# MINI_SAM_D51_005.net
KiCad netlist of a schematic drawn in EAGLE
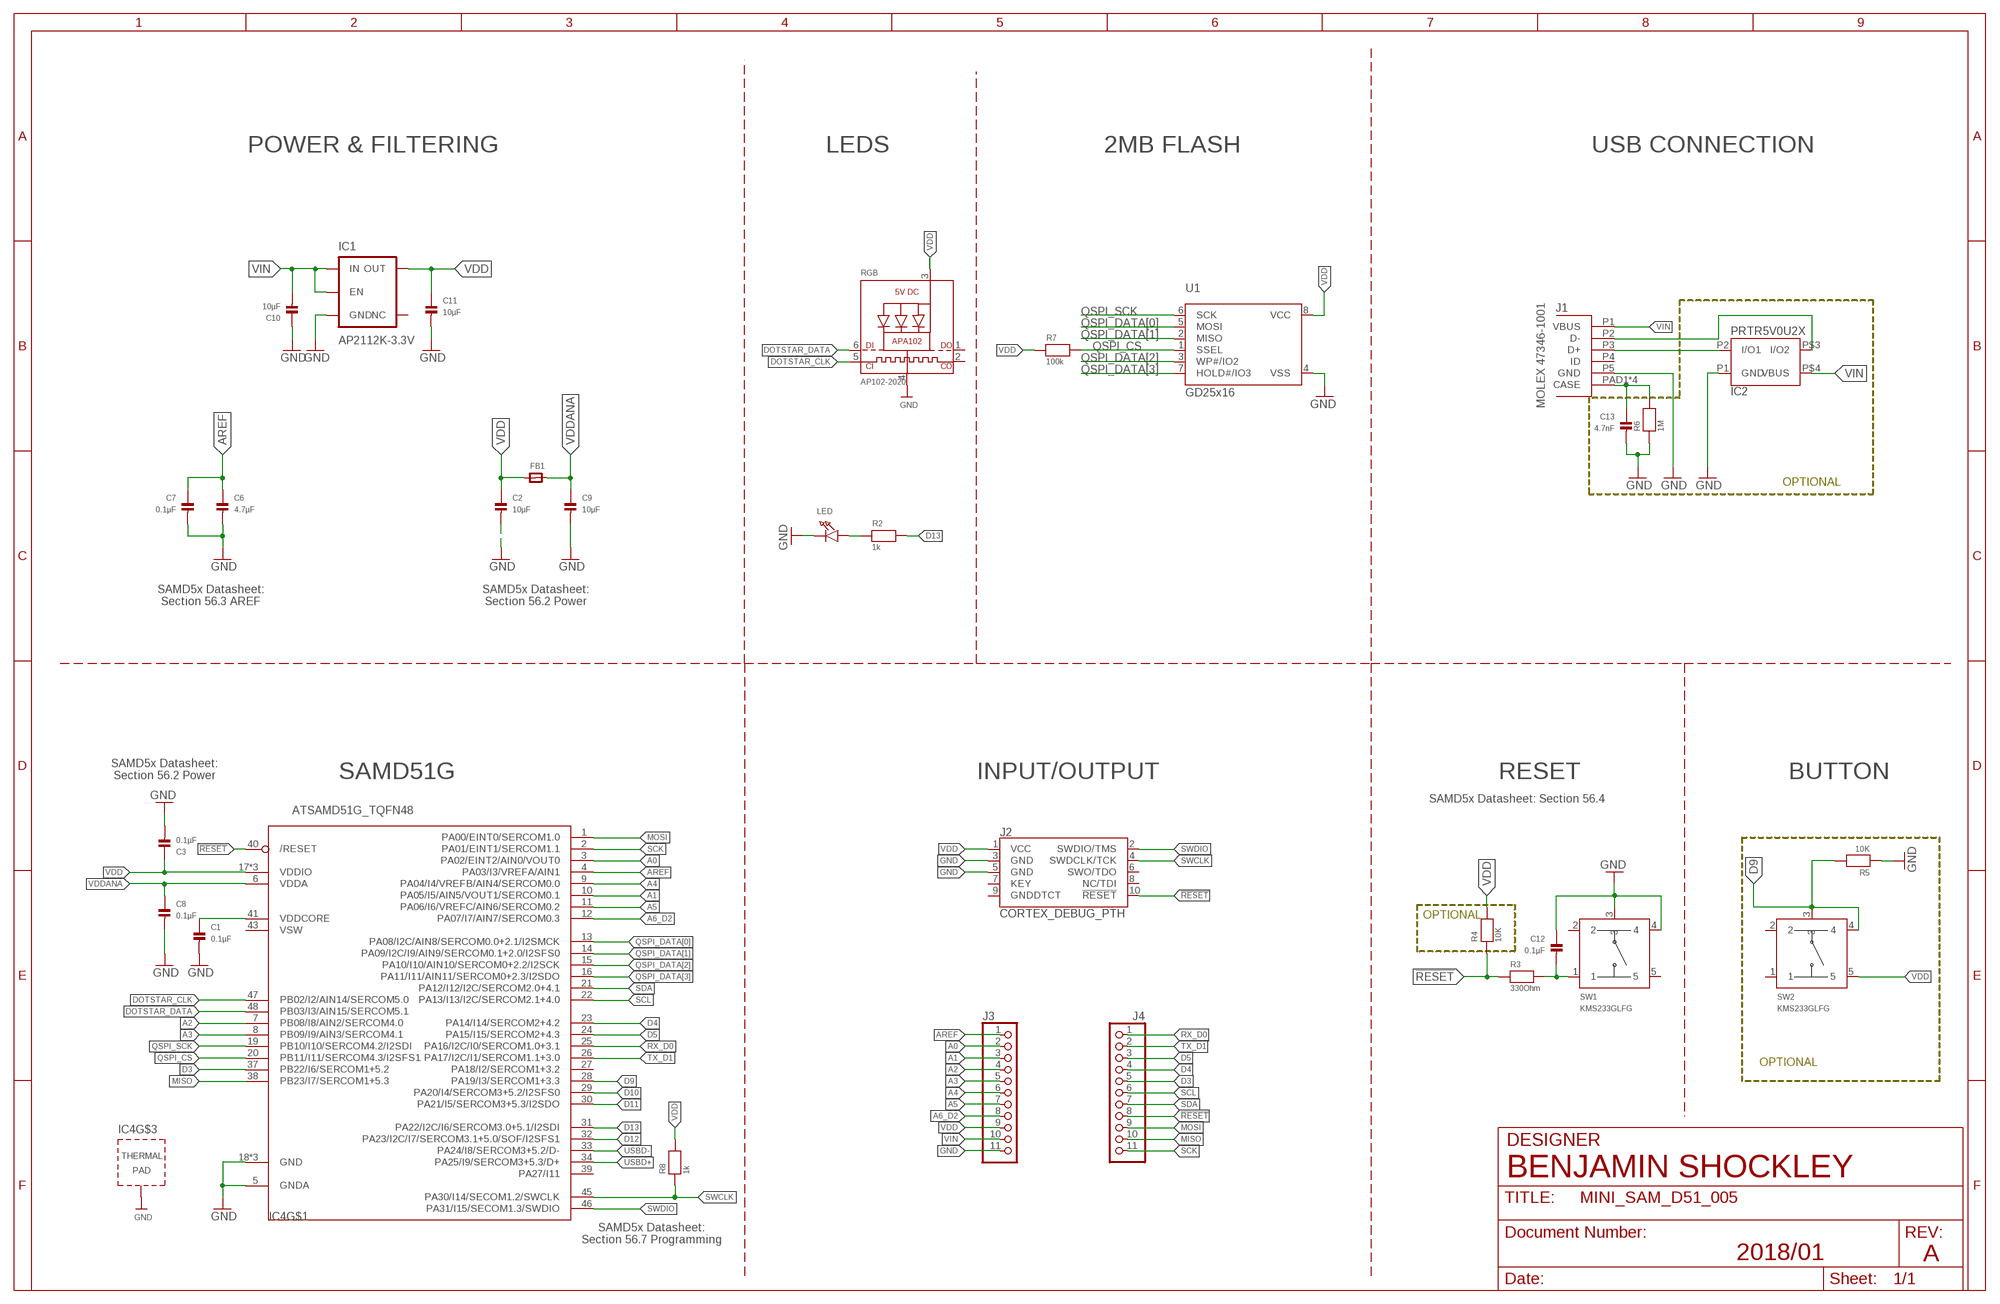
[diagram p0: schematic, sheet 1]

(export (version "E")
  (design (tool "Eeschema 10.0.6"))
  (components
    (comp (ref "C1")
      (value "0.1µF")
      (footprint "eagle-import:_0603MP")
      (libsource (lib "eagle-import") (part "CAP_CERAMIC_0603MP"))
    )
    (comp (ref "C2")
      (value "10µF")
      (footprint "eagle-import:_0603MP")
      (libsource (lib "eagle-import") (part "CAP_CERAMIC_0603MP"))
    )
    (comp (ref "C3")
      (value "0.1µF")
      (footprint "eagle-import:_0603MP")
      (libsource (lib "eagle-import") (part "CAP_CERAMIC_0603MP"))
    )
    (comp (ref "C6")
      (value "4.7µF")
      (footprint "eagle-import:_0603MP")
      (libsource (lib "eagle-import") (part "CAP_CERAMIC_0603MP"))
    )
    (comp (ref "C7")
      (value "0.1µF")
      (footprint "eagle-import:_0603MP")
      (libsource (lib "eagle-import") (part "CAP_CERAMIC_0603MP"))
    )
    (comp (ref "C8")
      (value "0.1µF")
      (footprint "eagle-import:_0603MP")
      (libsource (lib "eagle-import") (part "CAP_CERAMIC_0603MP"))
    )
    (comp (ref "C9")
      (value "10µF")
      (footprint "eagle-import:_0603MP")
      (libsource (lib "eagle-import") (part "CAP_CERAMIC_0603MP"))
    )
    (comp (ref "C10")
      (value "10µF")
      (footprint "eagle-import:_0603MP")
      (libsource (lib "eagle-import") (part "CAP_CERAMIC_0603MP"))
    )
    (comp (ref "C11")
      (value "10µF")
      (footprint "eagle-import:_0603MP")
      (libsource (lib "eagle-import") (part "CAP_CERAMIC_0603MP"))
    )
    (comp (ref "C12")
      (value "0.1µF")
      (footprint "eagle-import:_0603MP")
      (libsource (lib "eagle-import") (part "CAP_CERAMIC_0603MP"))
    )
    (comp (ref "C13")
      (value "4.7nF")
      (footprint "eagle-import:_0603MP")
      (libsource (lib "eagle-import") (part "CAP_CERAMIC_0603MP"))
    )
    (comp (ref "FB1")
      (value "FERRITE_0603MP")
      (footprint "eagle-import:_0603MP")
      (libsource (lib "eagle-import") (part "FERRITE_0603MP"))
    )
    (comp (ref "IC1")
      (value "AP2112K-3.3V")
      (footprint "eagle-import:SOT23-5")
      (libsource (lib "eagle-import") (part "V_REG_AP2112K-3.3V"))
    )
    (comp (ref "IC2")
      (value "PRTR5V0U2X")
      (footprint "eagle-import:SOT143B_REFLOW")
      (libsource (lib "eagle-import") (part "PRTR5V0U2X"))
    )
    (comp (ref "IC4")
      (value "ATSAMD51G_TQFN48")
      (footprint "eagle-import:TQFN48_7MM")
      (libsource (lib "eagle-import") (part "ATSAMD51G_TQFN48"))
    )
    (comp (ref "J1")
      (value "MOLEX_47346-100147346")
      (footprint "eagle-import:MOLEX_47346-1001")
      (libsource (lib "eagle-import") (part "MOLEX_47346-100147346"))
    )
    (comp (ref "J2")
      (value "CORTEX_DEBUG_PTH")
      (footprint "eagle-import:2X5-PTH-1.27MM")
      (libsource (lib "eagle-import") (part "CORTEX_DEBUG_PTH"))
    )
    (comp (ref "J3")
      (value "PINHD-1X111X11_SMT")
      (footprint "eagle-import:1X11_SMT")
      (libsource (lib "eagle-import") (part "PINHD-1X111X11_SMT"))
    )
    (comp (ref "J4")
      (value "PINHD-1X111X11_SMT")
      (footprint "eagle-import:1X11_SMT")
      (libsource (lib "eagle-import") (part "PINHD-1X111X11_SMT"))
    )
    (comp (ref "LED")
      (value "LED0603_NOOUTLINE")
      (footprint "eagle-import:CHIPLED_0603_NOOUTLINE")
      (libsource (lib "eagle-import") (part "LED0603_NOOUTLINE"))
    )
    (comp (ref "R2")
      (value "1k")
      (footprint "eagle-import:_0603MP")
      (libsource (lib "eagle-import") (part "RESISTOR_0603MP"))
    )
    (comp (ref "R3")
      (value "330Ohm")
      (footprint "eagle-import:_0603MP")
      (libsource (lib "eagle-import") (part "RESISTOR_0603MP"))
    )
    (comp (ref "R4")
      (value "10K")
      (footprint "eagle-import:_0603MP")
      (libsource (lib "eagle-import") (part "RESISTOR_0603MP"))
    )
    (comp (ref "R5")
      (value "10K")
      (footprint "eagle-import:_0603MP")
      (libsource (lib "eagle-import") (part "RESISTOR_0603MP"))
    )
    (comp (ref "R6")
      (value "1M")
      (footprint "eagle-import:_0603MP")
      (libsource (lib "eagle-import") (part "RESISTOR_0603MP"))
    )
    (comp (ref "R7")
      (value "100k")
      (footprint "eagle-import:_0603MP")
      (libsource (lib "eagle-import") (part "RESISTOR_0603MP"))
    )
    (comp (ref "R8")
      (value "1k")
      (footprint "eagle-import:_0603MP")
      (libsource (lib "eagle-import") (part "RESISTOR_0603MP"))
    )
    (comp (ref "RGB")
      (value "AP102-2020")
      (footprint "eagle-import:APA102_2020")
      (libsource (lib "eagle-import") (part "APA1022020"))
    )
    (comp (ref "SW1")
      (value "KMS233GLFG")
      (footprint "eagle-import:KMS_SWITCH")
      (libsource (lib "eagle-import") (part "KMS_SWITCHKMS"))
    )
    (comp (ref "SW2")
      (value "KMS233GLFG")
      (footprint "eagle-import:KMS_SWITCH")
      (libsource (lib "eagle-import") (part "KMS_SWITCHKMS"))
    )
    (comp (ref "U1")
      (value "GD25x16")
      (footprint "eagle-import:USON8")
      (libsource (lib "eagle-import") (part "SPIFLASH_8PINUX"))
    )
  )
  (nets
    (net (code "1") (name "/VSW") (class "Default")
      (node (ref "IC4") (pin "43") (pinfunction "VSW_43") (pintype "power_in"))
    )
    (net (code "2") (name "/~{RESET}") (class "Default")
      (node (ref "IC4") (pin "40") (pinfunction "/RESET_40") (pintype "bidirectional"))
      (node (ref "J2") (pin "10") (pinfunction "~{RESET}_10") (pintype "bidirectional"))
      (node (ref "J4") (pin "8") (pinfunction "8_8") (pintype "passive"))
      (node (ref "R3") (pin "1") (pinfunction "1_1") (pintype "passive"))
      (node (ref "R4") (pin "1") (pinfunction "1_1") (pintype "passive"))
    )
    (net (code "3") (name "A0") (class "Default")
      (node (ref "IC4") (pin "3") (pinfunction "PA02/EINT2/AIN0/VOUT0_3") (pintype "bidirectional"))
      (node (ref "J3") (pin "2") (pinfunction "2_2") (pintype "passive"))
    )
    (net (code "4") (name "A1") (class "Default")
      (node (ref "IC4") (pin "10") (pinfunction "PA05/I5/AIN5/VOUT1/SERCOM0.1_10") (pintype "bidirectional"))
      (node (ref "J3") (pin "3") (pinfunction "3_3") (pintype "passive"))
    )
    (net (code "5") (name "A2") (class "Default")
      (node (ref "IC4") (pin "7") (pinfunction "PB08/I8/AIN2/SERCOM4.0_7") (pintype "bidirectional"))
      (node (ref "J3") (pin "4") (pinfunction "4_4") (pintype "passive"))
    )
    (net (code "6") (name "A3") (class "Default")
      (node (ref "IC4") (pin "8") (pinfunction "PB09/I9/AIN3/SERCOM4.1_8") (pintype "bidirectional"))
      (node (ref "J3") (pin "5") (pinfunction "5_5") (pintype "passive"))
    )
    (net (code "7") (name "A4") (class "Default")
      (node (ref "IC4") (pin "9") (pinfunction "PA04/I4/VREFB/AIN4/SERCOM0.0_9") (pintype "bidirectional"))
      (node (ref "J3") (pin "6") (pinfunction "6_6") (pintype "passive"))
    )
    (net (code "8") (name "A5") (class "Default")
      (node (ref "IC4") (pin "11") (pinfunction "PA06/I6/VREFC/AIN6/SERCOM0.2_11") (pintype "bidirectional"))
      (node (ref "J3") (pin "7") (pinfunction "7_7") (pintype "passive"))
    )
    (net (code "9") (name "A6_D2") (class "Default")
      (node (ref "IC4") (pin "12") (pinfunction "PA07/I7/AIN7/SERCOM0.3_12") (pintype "bidirectional"))
      (node (ref "J3") (pin "8") (pinfunction "8_8") (pintype "passive"))
    )
    (net (code "10") (name "AREF") (class "Default")
      (node (ref "C6") (pin "1") (pinfunction "P$1_1") (pintype "passive"))
      (node (ref "C7") (pin "1") (pinfunction "P$1_1") (pintype "passive"))
      (node (ref "IC4") (pin "4") (pinfunction "PA03/I3/VREFA/AIN1_4") (pintype "bidirectional"))
      (node (ref "J3") (pin "1") (pinfunction "1_1") (pintype "passive"))
    )
    (net (code "11") (name "D3") (class "Default")
      (node (ref "IC4") (pin "37") (pinfunction "PB22/I6/SERCOM1+5.2_37") (pintype "bidirectional"))
      (node (ref "J4") (pin "5") (pinfunction "5_5") (pintype "passive"))
    )
    (net (code "12") (name "D4") (class "Default")
      (node (ref "IC4") (pin "23") (pinfunction "PA14/I14/SERCOM2+4.2_23") (pintype "bidirectional"))
      (node (ref "J4") (pin "4") (pinfunction "4_4") (pintype "passive"))
    )
    (net (code "13") (name "D5") (class "Default")
      (node (ref "IC4") (pin "24") (pinfunction "PA15/I15/SERCOM2+4.3_24") (pintype "bidirectional"))
      (node (ref "J4") (pin "3") (pinfunction "3_3") (pintype "passive"))
    )
    (net (code "14") (name "D9") (class "Default")
      (node (ref "IC4") (pin "28") (pinfunction "PA19/I3/SERCOM1+3.3_28") (pintype "bidirectional"))
      (node (ref "R5") (pin "2") (pinfunction "2_2") (pintype "passive"))
      (node (ref "SW2") (pin "3") (pinfunction "3_3") (pintype "bidirectional"))
      (node (ref "SW2") (pin "4") (pinfunction "4_4") (pintype "bidirectional"))
    )
    (net (code "15") (name "D10") (class "Default")
      (node (ref "IC4") (pin "29") (pinfunction "PA20/I4/SERCOM3+5.2/I2SFS0_29") (pintype "bidirectional"))
    )
    (net (code "16") (name "D11") (class "Default")
      (node (ref "IC4") (pin "30") (pinfunction "PA21/I5/SERCOM3+5.3/I2SDO_30") (pintype "bidirectional"))
    )
    (net (code "17") (name "D12") (class "Default")
      (node (ref "IC4") (pin "32") (pinfunction "PA23/I2C/I7/SERCOM3.1+5.0/SOF/I2SFS1_32") (pintype "bidirectional"))
    )
    (net (code "18") (name "D13") (class "Default")
      (node (ref "IC4") (pin "31") (pinfunction "PA22/I2C/I6/SERCOM3.0+5.1/I2SDI_31") (pintype "bidirectional"))
      (node (ref "R2") (pin "2") (pinfunction "2_2") (pintype "passive"))
    )
    (net (code "19") (name "DOTSTAR_CLK") (class "Default")
      (node (ref "IC4") (pin "47") (pinfunction "PB02/I2/AIN14/SERCOM5.0_47") (pintype "bidirectional"))
      (node (ref "RGB") (pin "5") (pinfunction "CKI_5") (pintype "input"))
    )
    (net (code "20") (name "DOTSTAR_DATA") (class "Default")
      (node (ref "IC4") (pin "48") (pinfunction "PB03/I3/AIN15/SERCOM5.1_48") (pintype "bidirectional"))
      (node (ref "RGB") (pin "6") (pinfunction "DI_6") (pintype "input"))
    )
    (net (code "21") (name "GND") (class "Default")
      (node (ref "C1") (pin "2") (pinfunction "P$2_2") (pintype "passive"))
      (node (ref "C10") (pin "1") (pinfunction "P$1_1") (pintype "passive"))
      (node (ref "C11") (pin "2") (pinfunction "P$2_2") (pintype "passive"))
      (node (ref "C12") (pin "1") (pinfunction "P$1_1") (pintype "passive"))
      (node (ref "C13") (pin "2") (pinfunction "P$2_2") (pintype "passive"))
      (node (ref "C2") (pin "2") (pinfunction "P$2_2") (pintype "passive"))
      (node (ref "C3") (pin "2") (pinfunction "P$2_2") (pintype "passive"))
      (node (ref "C6") (pin "2") (pinfunction "P$2_2") (pintype "passive"))
      (node (ref "C7") (pin "2") (pinfunction "P$2_2") (pintype "passive"))
      (node (ref "C8") (pin "2") (pinfunction "P$2_2") (pintype "passive"))
      (node (ref "C9") (pin "2") (pinfunction "P$2_2") (pintype "passive"))
      (node (ref "IC1") (pin "2") (pinfunction "GND_2") (pintype "input"))
      (node (ref "IC2") (pin "P1") (pinfunction "GND_P1") (pintype "bidirectional"))
      (node (ref "IC4") (pin "18") (pinfunction "GND_18") (pintype "power_in"))
      (node (ref "IC4") (pin "35") (pinfunction "GND_35") (pintype "power_in"))
      (node (ref "IC4") (pin "42") (pinfunction "GND_42") (pintype "power_in"))
      (node (ref "IC4") (pin "5") (pinfunction "GNDA_5") (pintype "power_in"))
      (node (ref "IC4") (pin "THERMAL") (pinfunction "TP_THERMAL") (pintype "power_in"))
      (node (ref "J1") (pin "P5") (pinfunction "GND_P5") (pintype "power_in"))
      (node (ref "J2") (pin "3") (pinfunction "GND_3") (pintype "bidirectional"))
      (node (ref "J2") (pin "5") (pinfunction "GND_5") (pintype "bidirectional"))
      (node (ref "J3") (pin "11") (pinfunction "11_11") (pintype "passive"))
      (node (ref "LED") (pin "C") (pinfunction "C_C") (pintype "passive"))
      (node (ref "R5") (pin "1") (pinfunction "1_1") (pintype "passive"))
      (node (ref "R6") (pin "1") (pinfunction "1_1") (pintype "passive"))
      (node (ref "RGB") (pin "4") (pinfunction "GND_4") (pintype "power_in"))
      (node (ref "SW1") (pin "3") (pinfunction "3_3") (pintype "bidirectional"))
      (node (ref "SW1") (pin "4") (pinfunction "4_4") (pintype "bidirectional"))
      (node (ref "U1") (pin "4") (pinfunction "VSS_4") (pintype "bidirectional"))
    )
    (net (code "22") (name "MISO") (class "Default")
      (node (ref "IC4") (pin "38") (pinfunction "PB23/I7/SERCOM1+5.3_38") (pintype "bidirectional"))
      (node (ref "J4") (pin "10") (pinfunction "10_10") (pintype "passive"))
    )
    (net (code "23") (name "MOSI") (class "Default")
      (node (ref "IC4") (pin "1") (pinfunction "PA00/EINT0/SERCOM1.0_1") (pintype "bidirectional"))
      (node (ref "J4") (pin "9") (pinfunction "9_9") (pintype "passive"))
    )
    (net (code "24") (name "Net-(C1-P$1)") (class "Default")
      (node (ref "C1") (pin "1") (pinfunction "P$1_1") (pintype "passive"))
      (node (ref "IC4") (pin "41") (pinfunction "VDDCORE_41") (pintype "power_in"))
    )
    (net (code "25") (name "Net-(C12-P$2)") (class "Default")
      (node (ref "C12") (pin "2") (pinfunction "P$2_2") (pintype "passive"))
      (node (ref "R3") (pin "2") (pinfunction "2_2") (pintype "passive"))
      (node (ref "SW1") (pin "1") (pinfunction "1_1") (pintype "bidirectional"))
    )
    (net (code "26") (name "Net-(C13-P$1)") (class "Default")
      (node (ref "C13") (pin "1") (pinfunction "P$1_1") (pintype "passive"))
      (node (ref "J1") (pin "PAD1") (pinfunction "CASE_PAD1") (pintype "bidirectional"))
      (node (ref "J1") (pin "PAD2") (pinfunction "CASE_PAD2") (pintype "bidirectional"))
      (node (ref "J1") (pin "PAD3") (pinfunction "CASE_PAD3") (pintype "bidirectional"))
      (node (ref "J1") (pin "PAD4") (pinfunction "CASE_PAD4") (pintype "bidirectional"))
      (node (ref "R6") (pin "2") (pinfunction "2_2") (pintype "passive"))
    )
    (net (code "27") (name "Net-(LED-PadA)") (class "Default")
      (node (ref "LED") (pin "A") (pinfunction "A_A") (pintype "passive"))
      (node (ref "R2") (pin "1") (pinfunction "1_1") (pintype "passive"))
    )
    (net (code "28") (name "QSPI_CS") (class "Default")
      (node (ref "IC4") (pin "20") (pinfunction "PB11/I11/SERCOM4.3/I2SFS1_20") (pintype "bidirectional"))
      (node (ref "R7") (pin "2") (pinfunction "2_2") (pintype "passive"))
      (node (ref "U1") (pin "1") (pinfunction "SSEL_1") (pintype "bidirectional"))
    )
    (net (code "29") (name "QSPI_DATA[0]") (class "Default")
      (node (ref "IC4") (pin "13") (pinfunction "PA08/I2C/AIN8/SERCOM0.0+2.1/I2SMCK_13") (pintype "bidirectional"))
      (node (ref "U1") (pin "5") (pinfunction "MOSI_5") (pintype "bidirectional"))
    )
    (net (code "30") (name "QSPI_DATA[1]") (class "Default")
      (node (ref "IC4") (pin "14") (pinfunction "PA09/I2C/I9/AIN9/SERCOM0.1+2.0/I2SFS0_14") (pintype "bidirectional"))
      (node (ref "U1") (pin "2") (pinfunction "MISO_2") (pintype "bidirectional"))
    )
    (net (code "31") (name "QSPI_DATA[2]") (class "Default")
      (node (ref "IC4") (pin "15") (pinfunction "PA10/I10/AIN10/SERCOM0+2.2/I2SCK_15") (pintype "bidirectional"))
      (node (ref "U1") (pin "3") (pinfunction "WP#/IO2_3") (pintype "bidirectional"))
    )
    (net (code "32") (name "QSPI_DATA[3]") (class "Default")
      (node (ref "IC4") (pin "16") (pinfunction "PA11/I11/AIN11/SERCOM0+2.3/I2SDO_16") (pintype "bidirectional"))
      (node (ref "U1") (pin "7") (pinfunction "HOLD#/IO3_7") (pintype "bidirectional"))
    )
    (net (code "33") (name "QSPI_SCK") (class "Default")
      (node (ref "IC4") (pin "19") (pinfunction "PB10/I10/SERCOM4.2/I2SDI_19") (pintype "bidirectional"))
      (node (ref "U1") (pin "6") (pinfunction "SCK_6") (pintype "bidirectional"))
    )
    (net (code "34") (name "RX_D0") (class "Default")
      (node (ref "IC4") (pin "25") (pinfunction "PA16/I2C/I0/SERCOM1.0+3.1_25") (pintype "bidirectional"))
      (node (ref "J4") (pin "1") (pinfunction "1_1") (pintype "passive"))
    )
    (net (code "35") (name "SCK") (class "Default")
      (node (ref "IC4") (pin "2") (pinfunction "PA01/EINT1/SERCOM1.1_2") (pintype "bidirectional"))
      (node (ref "J4") (pin "11") (pinfunction "11_11") (pintype "passive"))
    )
    (net (code "36") (name "SCL") (class "Default")
      (node (ref "IC4") (pin "22") (pinfunction "PA13/I13/I2C/SERCOM2.1+4.0_22") (pintype "bidirectional"))
      (node (ref "J4") (pin "6") (pinfunction "6_6") (pintype "passive"))
    )
    (net (code "37") (name "SDA") (class "Default")
      (node (ref "IC4") (pin "21") (pinfunction "PA12/I12/I2C/SERCOM2.0+4.1_21") (pintype "bidirectional"))
      (node (ref "J4") (pin "7") (pinfunction "7_7") (pintype "passive"))
    )
    (net (code "38") (name "SWCLK") (class "Default")
      (node (ref "IC4") (pin "45") (pinfunction "PA30/I14/SECOM1.2/SWCLK_45") (pintype "bidirectional"))
      (node (ref "J2") (pin "4") (pinfunction "SWDCLK/TCK_4") (pintype "bidirectional"))
      (node (ref "R8") (pin "1") (pinfunction "1_1") (pintype "passive"))
    )
    (net (code "39") (name "SWDIO") (class "Default")
      (node (ref "IC4") (pin "46") (pinfunction "PA31/I15/SECOM1.3/SWDIO_46") (pintype "bidirectional"))
      (node (ref "J2") (pin "2") (pinfunction "SWDIO/TMS_2") (pintype "bidirectional"))
    )
    (net (code "40") (name "TX_D1") (class "Default")
      (node (ref "IC4") (pin "26") (pinfunction "PA17/I2C/I1/SERCOM1.1+3.0_26") (pintype "bidirectional"))
      (node (ref "J4") (pin "2") (pinfunction "2_2") (pintype "passive"))
    )
    (net (code "41") (name "USBD+") (class "Default")
      (node (ref "IC2") (pin "P2") (pinfunction "I/O1_P2") (pintype "bidirectional"))
      (node (ref "IC4") (pin "34") (pinfunction "PA25/I9/SERCOM3+5.3/D+_34") (pintype "bidirectional"))
      (node (ref "J1") (pin "P3") (pinfunction "D+_P3") (pintype "bidirectional"))
    )
    (net (code "42") (name "USBD-") (class "Default")
      (node (ref "IC2") (pin "P$3") (pinfunction "I/O2_P$3") (pintype "bidirectional"))
      (node (ref "IC4") (pin "33") (pinfunction "PA24/I8/SERCOM3+5.2/D-_33") (pintype "bidirectional"))
      (node (ref "J1") (pin "P2") (pinfunction "D-_P2") (pintype "bidirectional"))
    )
    (net (code "43") (name "VDD") (class "Default")
      (node (ref "C11") (pin "1") (pinfunction "P$1_1") (pintype "passive"))
      (node (ref "C2") (pin "1") (pinfunction "P$1_1") (pintype "passive"))
      (node (ref "C3") (pin "1") (pinfunction "P$1_1") (pintype "passive"))
      (node (ref "FB1") (pin "1") (pinfunction "P$1_1") (pintype "passive"))
      (node (ref "IC1") (pin "5") (pinfunction "OUT_5") (pintype "passive"))
      (node (ref "IC4") (pin "17") (pinfunction "VDDIO_17") (pintype "power_in"))
      (node (ref "IC4") (pin "36") (pinfunction "VDDIO_36") (pintype "power_in"))
      (node (ref "IC4") (pin "44") (pinfunction "VDDIO_44") (pintype "power_in"))
      (node (ref "J2") (pin "1") (pinfunction "VCC_1") (pintype "bidirectional"))
      (node (ref "J3") (pin "9") (pinfunction "9_9") (pintype "passive"))
      (node (ref "R4") (pin "2") (pinfunction "2_2") (pintype "passive"))
      (node (ref "R7") (pin "1") (pinfunction "1_1") (pintype "passive"))
      (node (ref "R8") (pin "2") (pinfunction "2_2") (pintype "passive"))
      (node (ref "RGB") (pin "3") (pinfunction "VDD_3") (pintype "power_in"))
      (node (ref "SW2") (pin "5") (pinfunction "5_5") (pintype "bidirectional"))
      (node (ref "U1") (pin "8") (pinfunction "VCC_8") (pintype "bidirectional"))
    )
    (net (code "44") (name "VDDANA") (class "Default")
      (node (ref "C8") (pin "1") (pinfunction "P$1_1") (pintype "passive"))
      (node (ref "C9") (pin "1") (pinfunction "P$1_1") (pintype "passive"))
      (node (ref "FB1") (pin "2") (pinfunction "P$2_2") (pintype "passive"))
      (node (ref "IC4") (pin "6") (pinfunction "VDDA_6") (pintype "power_in"))
    )
    (net (code "45") (name "VIN") (class "Default")
      (node (ref "C10") (pin "2") (pinfunction "P$2_2") (pintype "passive"))
      (node (ref "IC1") (pin "1") (pinfunction "IN_1") (pintype "input"))
      (node (ref "IC1") (pin "3") (pinfunction "EN_3") (pintype "input"))
      (node (ref "IC2") (pin "P$4") (pinfunction "VBUS_P$4") (pintype "bidirectional"))
      (node (ref "J1") (pin "P1") (pinfunction "VBUS_P1") (pintype "power_in"))
      (node (ref "J3") (pin "10") (pinfunction "10_10") (pintype "passive"))
    )
    (net (code "46") (name "unconnected-(IC1-NC-Pad4)") (class "Default")
      (node (ref "IC1") (pin "4") (pinfunction "NC_4") (pintype "input"))
    )
    (net (code "47") (name "unconnected-(IC4A-PA18{slash}I2{slash}SERCOM1+3.2-Pad27)") (class "Default")
      (node (ref "IC4") (pin "27") (pinfunction "PA18/I2/SERCOM1+3.2_27") (pintype "bidirectional"))
    )
    (net (code "48") (name "unconnected-(IC4A-PA27{slash}I11-Pad39)") (class "Default")
      (node (ref "IC4") (pin "39") (pinfunction "PA27/I11_39") (pintype "bidirectional"))
    )
    (net (code "49") (name "unconnected-(J1-ID-PadP4)") (class "Default")
      (node (ref "J1") (pin "P4") (pinfunction "ID_P4") (pintype "bidirectional"))
    )
    (net (code "50") (name "unconnected-(J2-GNDDTCT-Pad9)") (class "Default")
      (node (ref "J2") (pin "9") (pinfunction "GNDDTCT_9") (pintype "bidirectional"))
    )
    (net (code "51") (name "unconnected-(J2-KEY-Pad7)") (class "Default")
      (node (ref "J2") (pin "7") (pinfunction "KEY_7") (pintype "bidirectional"))
    )
    (net (code "52") (name "unconnected-(J2-NC{slash}TDI-Pad8)") (class "Default")
      (node (ref "J2") (pin "8") (pinfunction "NC/TDI_8") (pintype "bidirectional"))
    )
    (net (code "53") (name "unconnected-(J2-SWO{slash}TDO-Pad6)") (class "Default")
      (node (ref "J2") (pin "6") (pinfunction "SWO/TDO_6") (pintype "bidirectional"))
    )
    (net (code "54") (name "unconnected-(RGB-CKO-Pad2)") (class "Default")
      (node (ref "RGB") (pin "2") (pinfunction "CKO_2") (pintype "output"))
    )
    (net (code "55") (name "unconnected-(RGB-DO-Pad1)") (class "Default")
      (node (ref "RGB") (pin "1") (pinfunction "DO_1") (pintype "output"))
    )
    (net (code "56") (name "unconnected-(SW1-Pad2)") (class "Default")
      (node (ref "SW1") (pin "2") (pinfunction "2_2") (pintype "bidirectional"))
    )
    (net (code "57") (name "unconnected-(SW1-Pad5)") (class "Default")
      (node (ref "SW1") (pin "5") (pinfunction "5_5") (pintype "bidirectional"))
    )
    (net (code "58") (name "unconnected-(SW2-Pad1)") (class "Default")
      (node (ref "SW2") (pin "1") (pinfunction "1_1") (pintype "bidirectional"))
    )
    (net (code "59") (name "unconnected-(SW2-Pad2)") (class "Default")
      (node (ref "SW2") (pin "2") (pinfunction "2_2") (pintype "bidirectional"))
    )
  )
)
